# CPU_POWER.net
KiCad netlist of a schematic drawn in Altium Designer
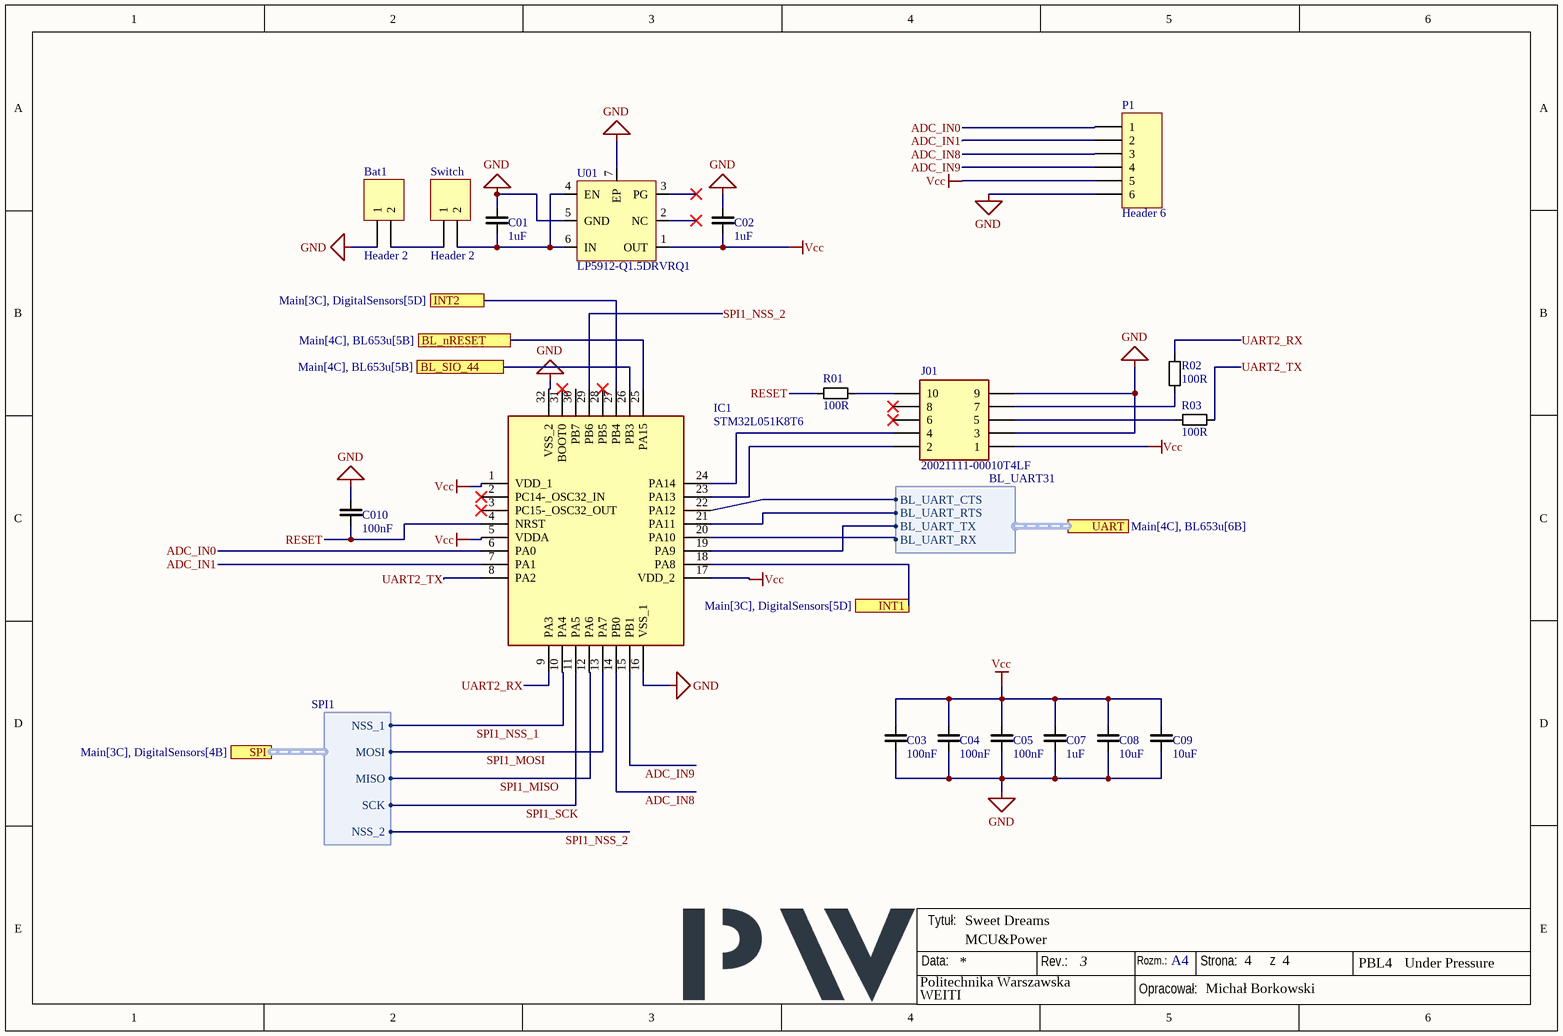
[diagram p0: CPU&POWER.SchDoc]

(export (version "E")
  (design (tool "Eeschema 10.0.6"))
  (components
    (comp (ref "Bat1")
      (value "Header 2")
      (footprint "HDR1X2")
      (description "Header, 2-Pin")
      (fields (field (name "PUBLISHER") "Altium Limited"))
      (libsource (lib "Miscellaneous Connectors") (part "Header 2"))
    )
    (comp (ref "C01")
      (value "1uF")
      (footprint "0402_CAP")
      (description "Ceramic capacitor")
      (libsource (lib "Cap") (part "Cap"))
    )
    (comp (ref "C02")
      (value "1uF")
      (footprint "0402_CAP")
      (description "Ceramic capacitor")
      (libsource (lib "Cap") (part "Cap"))
    )
    (comp (ref "C03")
      (value "100nF")
      (footprint "0402_CAP")
      (description "Ceramic capacitor")
      (libsource (lib "Cap") (part "Cap"))
    )
    (comp (ref "C04")
      (value "100nF")
      (footprint "0402_CAP")
      (description "Ceramic capacitor")
      (libsource (lib "Cap") (part "Cap"))
    )
    (comp (ref "C05")
      (value "100nF")
      (footprint "0402_CAP")
      (description "Ceramic capacitor")
      (libsource (lib "Cap") (part "Cap"))
    )
    (comp (ref "C07")
      (value "1uF")
      (footprint "0402_CAP")
      (description "Ceramic capacitor")
      (libsource (lib "Cap") (part "Cap"))
    )
    (comp (ref "C08")
      (value "10uF")
      (footprint "0402_CAP")
      (description "Ceramic capacitor")
      (libsource (lib "Cap") (part "Cap"))
    )
    (comp (ref "C09")
      (value "10uF")
      (footprint "0402_CAP")
      (description "Ceramic capacitor")
      (libsource (lib "Cap") (part "Cap"))
    )
    (comp (ref "C010")
      (value "100nF")
      (footprint "0402_CAP")
      (description "Ceramic capacitor")
      (libsource (lib "Cap") (part "Cap"))
    )
    (comp (ref "IC1")
      (value "STM32L051K8T6")
      (footprint "SamacSys:QFP80P900X900X160-32N")
      (description "Integrated Circuit")
      (fields (field (name "MOUSER PART NUMBER") "511-STM32L051K8T6"))
      (libsource (lib "SamacSys") (part "STM32L051K8T6"))
    )
    (comp (ref "J01")
      (value "20021111-00010T4LF")
      (footprint "HDRV10W41P127_2X5_635X343X575P_m")
      (description "Connector")
      (fields (field (name "MOUSER PART NUMBER") "649-221111-00010T4LF"))
      (libsource (lib "SamacSys") (part "20021111-00010T4LF"))
    )
    (comp (ref "P1")
      (value "Header 6")
      (footprint "HDR1X6")
      (description "Header, 6-Pin")
      (fields (field (name "PUBLISHER") "Altium Limited"))
      (libsource (lib "Miscellaneous Connectors") (part "Header 6"))
    )
    (comp (ref "R01")
      (value "100R")
      (footprint "0402_RES")
      (description "Resistor")
      (libsource (lib "RES") (part "RES"))
    )
    (comp (ref "R02")
      (value "100R")
      (footprint "0402_RES")
      (description "Resistor")
      (libsource (lib "RES") (part "RES"))
    )
    (comp (ref "R03")
      (value "100R")
      (footprint "0402_RES")
      (description "Resistor")
      (libsource (lib "RES") (part "RES"))
    )
    (comp (ref "Switch")
      (value "Header 2")
      (footprint "HDR1X2")
      (description "Header, 2-Pin")
      (fields (field (name "PUBLISHER") "Altium Limited"))
      (libsource (lib "Miscellaneous Connectors") (part "Header 2"))
    )
    (comp (ref "U01")
      (value "LP5912-Q1.5DRVRQ1")
      (footprint "SON65P200X200X80-7N_m")
      (libsource (lib "parts1") (part "STAB"))
    )
  )
  (nets
    (net (code "3") (name "/ADC_IN0") (class "Default")
      (node (ref "IC1") (pin "6") (pinfunction "PA0_6") (pintype "passive"))
      (node (ref "P1") (pin "1") (pinfunction "1_1") (pintype "passive"))
    )
    (net (code "4") (name "/ADC_IN1") (class "Default")
      (node (ref "IC1") (pin "7") (pinfunction "PA1_7") (pintype "passive"))
      (node (ref "P1") (pin "2") (pinfunction "2_2") (pintype "passive"))
    )
    (net (code "5") (name "/ADC_IN8") (class "Default")
      (node (ref "IC1") (pin "14") (pinfunction "PB0_14") (pintype "passive"))
      (node (ref "P1") (pin "3") (pinfunction "3_3") (pintype "passive"))
    )
    (net (code "6") (name "/ADC_IN9") (class "Default")
      (node (ref "IC1") (pin "15") (pinfunction "PB1_15") (pintype "passive"))
      (node (ref "P1") (pin "4") (pinfunction "4_4") (pintype "passive"))
    )
    (net (code "7") (name "/BL_SIO_44") (class "Default")
      (node (ref "IC1") (pin "26") (pinfunction "PB3_26") (pintype "passive"))
    )
    (net (code "8") (name "/BL_UART_CTS") (class "Default")
      (node (ref "IC1") (pin "22") (pinfunction "PA12_22") (pintype "passive"))
    )
    (net (code "9") (name "/BL_UART_RTS") (class "Default")
      (node (ref "IC1") (pin "21") (pinfunction "PA11_21") (pintype "passive"))
    )
    (net (code "10") (name "/BL_UART_RX") (class "Default")
      (node (ref "IC1") (pin "20") (pinfunction "PA10_20") (pintype "passive"))
    )
    (net (code "11") (name "/BL_UART_TX") (class "Default")
      (node (ref "IC1") (pin "19") (pinfunction "PA9_19") (pintype "passive"))
    )
    (net (code "12") (name "/BL_nRESET") (class "Default")
      (node (ref "IC1") (pin "25") (pinfunction "PA15_25") (pintype "passive"))
    )
    (net (code "13") (name "/INT1") (class "Default")
      (node (ref "IC1") (pin "18") (pinfunction "PA8_18") (pintype "passive"))
    )
    (net (code "14") (name "/INT2") (class "Default")
      (node (ref "IC1") (pin "27") (pinfunction "PB4_27") (pintype "passive"))
    )
    (net (code "15") (name "/RESET") (class "Default")
      (node (ref "C010") (pin "1") (pinfunction "1_1") (pintype "passive"))
      (node (ref "IC1") (pin "4") (pinfunction "NRST_4") (pintype "passive"))
      (node (ref "R01") (pin "1") (pinfunction "1_1") (pintype "passive"))
    )
    (net (code "16") (name "/SCK") (class "Default")
      (node (ref "IC1") (pin "11") (pinfunction "PA5_11") (pintype "passive"))
    )
    (net (code "17") (name "/SPI1_MISO") (class "Default")
      (node (ref "IC1") (pin "12") (pinfunction "PA6_12") (pintype "passive"))
    )
    (net (code "18") (name "/SPI1_MOSI") (class "Default")
      (node (ref "IC1") (pin "13") (pinfunction "PA7_13") (pintype "passive"))
    )
    (net (code "19") (name "/SPI1_NSS_1") (class "Default")
      (node (ref "IC1") (pin "10") (pinfunction "PA4_10") (pintype "passive"))
    )
    (net (code "20") (name "/SPI1_NSS_2") (class "Default")
      (node (ref "IC1") (pin "29") (pinfunction "PB6_29") (pintype "passive"))
    )
    (net (code "22") (name "/UART2_RX") (class "Default")
      (node (ref "IC1") (pin "9") (pinfunction "PA3_9") (pintype "passive"))
      (node (ref "R02") (pin "2") (pinfunction "2_2") (pintype "passive"))
    )
    (net (code "23") (name "/UART2_TX") (class "Default")
      (node (ref "IC1") (pin "8") (pinfunction "PA2_8") (pintype "passive"))
      (node (ref "R03") (pin "1") (pinfunction "1_1") (pintype "passive"))
    )
    (net (code "26") (name "GND") (class "Default")
      (node (ref "Bat1") (pin "1") (pinfunction "1_1") (pintype "passive"))
      (node (ref "C01") (pin "2") (pinfunction "2_2") (pintype "passive"))
      (node (ref "C010") (pin "2") (pinfunction "2_2") (pintype "passive"))
      (node (ref "C02") (pin "2") (pinfunction "2_2") (pintype "passive"))
      (node (ref "C03") (pin "1") (pinfunction "1_1") (pintype "passive"))
      (node (ref "C04") (pin "1") (pinfunction "1_1") (pintype "passive"))
      (node (ref "C05") (pin "1") (pinfunction "1_1") (pintype "passive"))
      (node (ref "C07") (pin "1") (pinfunction "1_1") (pintype "passive"))
      (node (ref "C08") (pin "1") (pinfunction "1_1") (pintype "passive"))
      (node (ref "C09") (pin "1") (pinfunction "1_1") (pintype "passive"))
      (node (ref "IC1") (pin "16") (pinfunction "VSS_1_16") (pintype "passive"))
      (node (ref "IC1") (pin "32") (pinfunction "VSS_2_32") (pintype "passive"))
      (node (ref "J01") (pin "3") (pinfunction "3_3") (pintype "passive"))
      (node (ref "J01") (pin "9") (pinfunction "9_9") (pintype "passive"))
      (node (ref "P1") (pin "6") (pinfunction "6_6") (pintype "passive"))
      (node (ref "U01") (pin "5") (pinfunction "GND_5") (pintype "passive"))
      (node (ref "U01") (pin "7") (pinfunction "EP_7") (pintype "passive"))
    )
    (net (code "27") (name "Net-(Bat1-Pad2)") (class "Default")
      (node (ref "Bat1") (pin "2") (pinfunction "2_2") (pintype "passive"))
      (node (ref "Switch") (pin "1") (pinfunction "1_1") (pintype "passive"))
    )
    (net (code "28") (name "Net-(IC1-PA13)") (class "Default")
      (node (ref "IC1") (pin "23") (pinfunction "PA13_23") (pintype "passive"))
      (node (ref "J01") (pin "2") (pinfunction "2_2") (pintype "passive"))
    )
    (net (code "29") (name "Net-(IC1-PA14)") (class "Default")
      (node (ref "IC1") (pin "24") (pinfunction "PA14_24") (pintype "passive"))
      (node (ref "J01") (pin "4") (pinfunction "4_4") (pintype "passive"))
    )
    (net (code "30") (name "Net-(J01-Pad5)") (class "Default")
      (node (ref "J01") (pin "5") (pinfunction "5_5") (pintype "passive"))
      (node (ref "R03") (pin "2") (pinfunction "2_2") (pintype "passive"))
    )
    (net (code "31") (name "Net-(J01-Pad7)") (class "Default")
      (node (ref "J01") (pin "7") (pinfunction "7_7") (pintype "passive"))
      (node (ref "R02") (pin "1") (pinfunction "1_1") (pintype "passive"))
    )
    (net (code "32") (name "Net-(J01-Pad10)") (class "Default")
      (node (ref "J01") (pin "10") (pinfunction "10_10") (pintype "passive"))
      (node (ref "R01") (pin "2") (pinfunction "2_2") (pintype "passive"))
    )
    (net (code "33") (name "Net-(U01-EN)") (class "Default")
      (node (ref "C01") (pin "1") (pinfunction "1_1") (pintype "passive"))
      (node (ref "Switch") (pin "2") (pinfunction "2_2") (pintype "passive"))
      (node (ref "U01") (pin "4") (pinfunction "EN_4") (pintype "passive"))
      (node (ref "U01") (pin "6") (pinfunction "IN_6") (pintype "passive"))
    )
    (net (code "34") (name "Vcc") (class "Default")
      (node (ref "C02") (pin "1") (pinfunction "1_1") (pintype "passive"))
      (node (ref "C03") (pin "2") (pinfunction "2_2") (pintype "passive"))
      (node (ref "C04") (pin "2") (pinfunction "2_2") (pintype "passive"))
      (node (ref "C05") (pin "2") (pinfunction "2_2") (pintype "passive"))
      (node (ref "C07") (pin "2") (pinfunction "2_2") (pintype "passive"))
      (node (ref "C08") (pin "2") (pinfunction "2_2") (pintype "passive"))
      (node (ref "C09") (pin "2") (pinfunction "2_2") (pintype "passive"))
      (node (ref "IC1") (pin "1") (pinfunction "VDD_1_1") (pintype "passive"))
      (node (ref "IC1") (pin "17") (pinfunction "VDD_2_17") (pintype "passive"))
      (node (ref "IC1") (pin "5") (pinfunction "VDDA_5") (pintype "passive"))
      (node (ref "J01") (pin "1") (pinfunction "1_1") (pintype "passive"))
      (node (ref "P1") (pin "5") (pinfunction "5_5") (pintype "passive"))
      (node (ref "U01") (pin "1") (pinfunction "OUT_1") (pintype "passive"))
    )
    (net (code "35") (name "unconnected-(IC1-BOOT0-Pad31)") (class "Default")
      (node (ref "IC1") (pin "31") (pinfunction "BOOT0_31") (pintype "passive+no_connect"))
    )
    (net (code "36") (name "unconnected-(IC1-PB5-Pad28)") (class "Default")
      (node (ref "IC1") (pin "28") (pinfunction "PB5_28") (pintype "passive+no_connect"))
    )
    (net (code "37") (name "unconnected-(IC1-PB7-Pad30)") (class "Default")
      (node (ref "IC1") (pin "30") (pinfunction "PB7_30") (pintype "passive"))
    )
    (net (code "38") (name "unconnected-(IC1-PC14-_OSC32_IN-Pad2)") (class "Default")
      (node (ref "IC1") (pin "2") (pinfunction "PC14-_OSC32_IN_2") (pintype "passive+no_connect"))
    )
    (net (code "39") (name "unconnected-(IC1-PC15-_OSC32_OUT-Pad3)") (class "Default")
      (node (ref "IC1") (pin "3") (pinfunction "PC15-_OSC32_OUT_3") (pintype "passive+no_connect"))
    )
    (net (code "40") (name "unconnected-(J01-Pad6)") (class "Default")
      (node (ref "J01") (pin "6") (pinfunction "6_6") (pintype "passive+no_connect"))
    )
    (net (code "41") (name "unconnected-(J01-Pad8)") (class "Default")
      (node (ref "J01") (pin "8") (pinfunction "8_8") (pintype "passive+no_connect"))
    )
    (net (code "42") (name "unconnected-(U01-NC-Pad2)") (class "Default")
      (node (ref "U01") (pin "2") (pinfunction "NC_2") (pintype "passive+no_connect"))
    )
    (net (code "43") (name "unconnected-(U01-PG-Pad3)") (class "Default")
      (node (ref "U01") (pin "3") (pinfunction "PG_3") (pintype "passive+no_connect"))
    )
  )
)
